# SUMO_AUTO.net
KiCad netlist of a schematic drawn in EAGLE
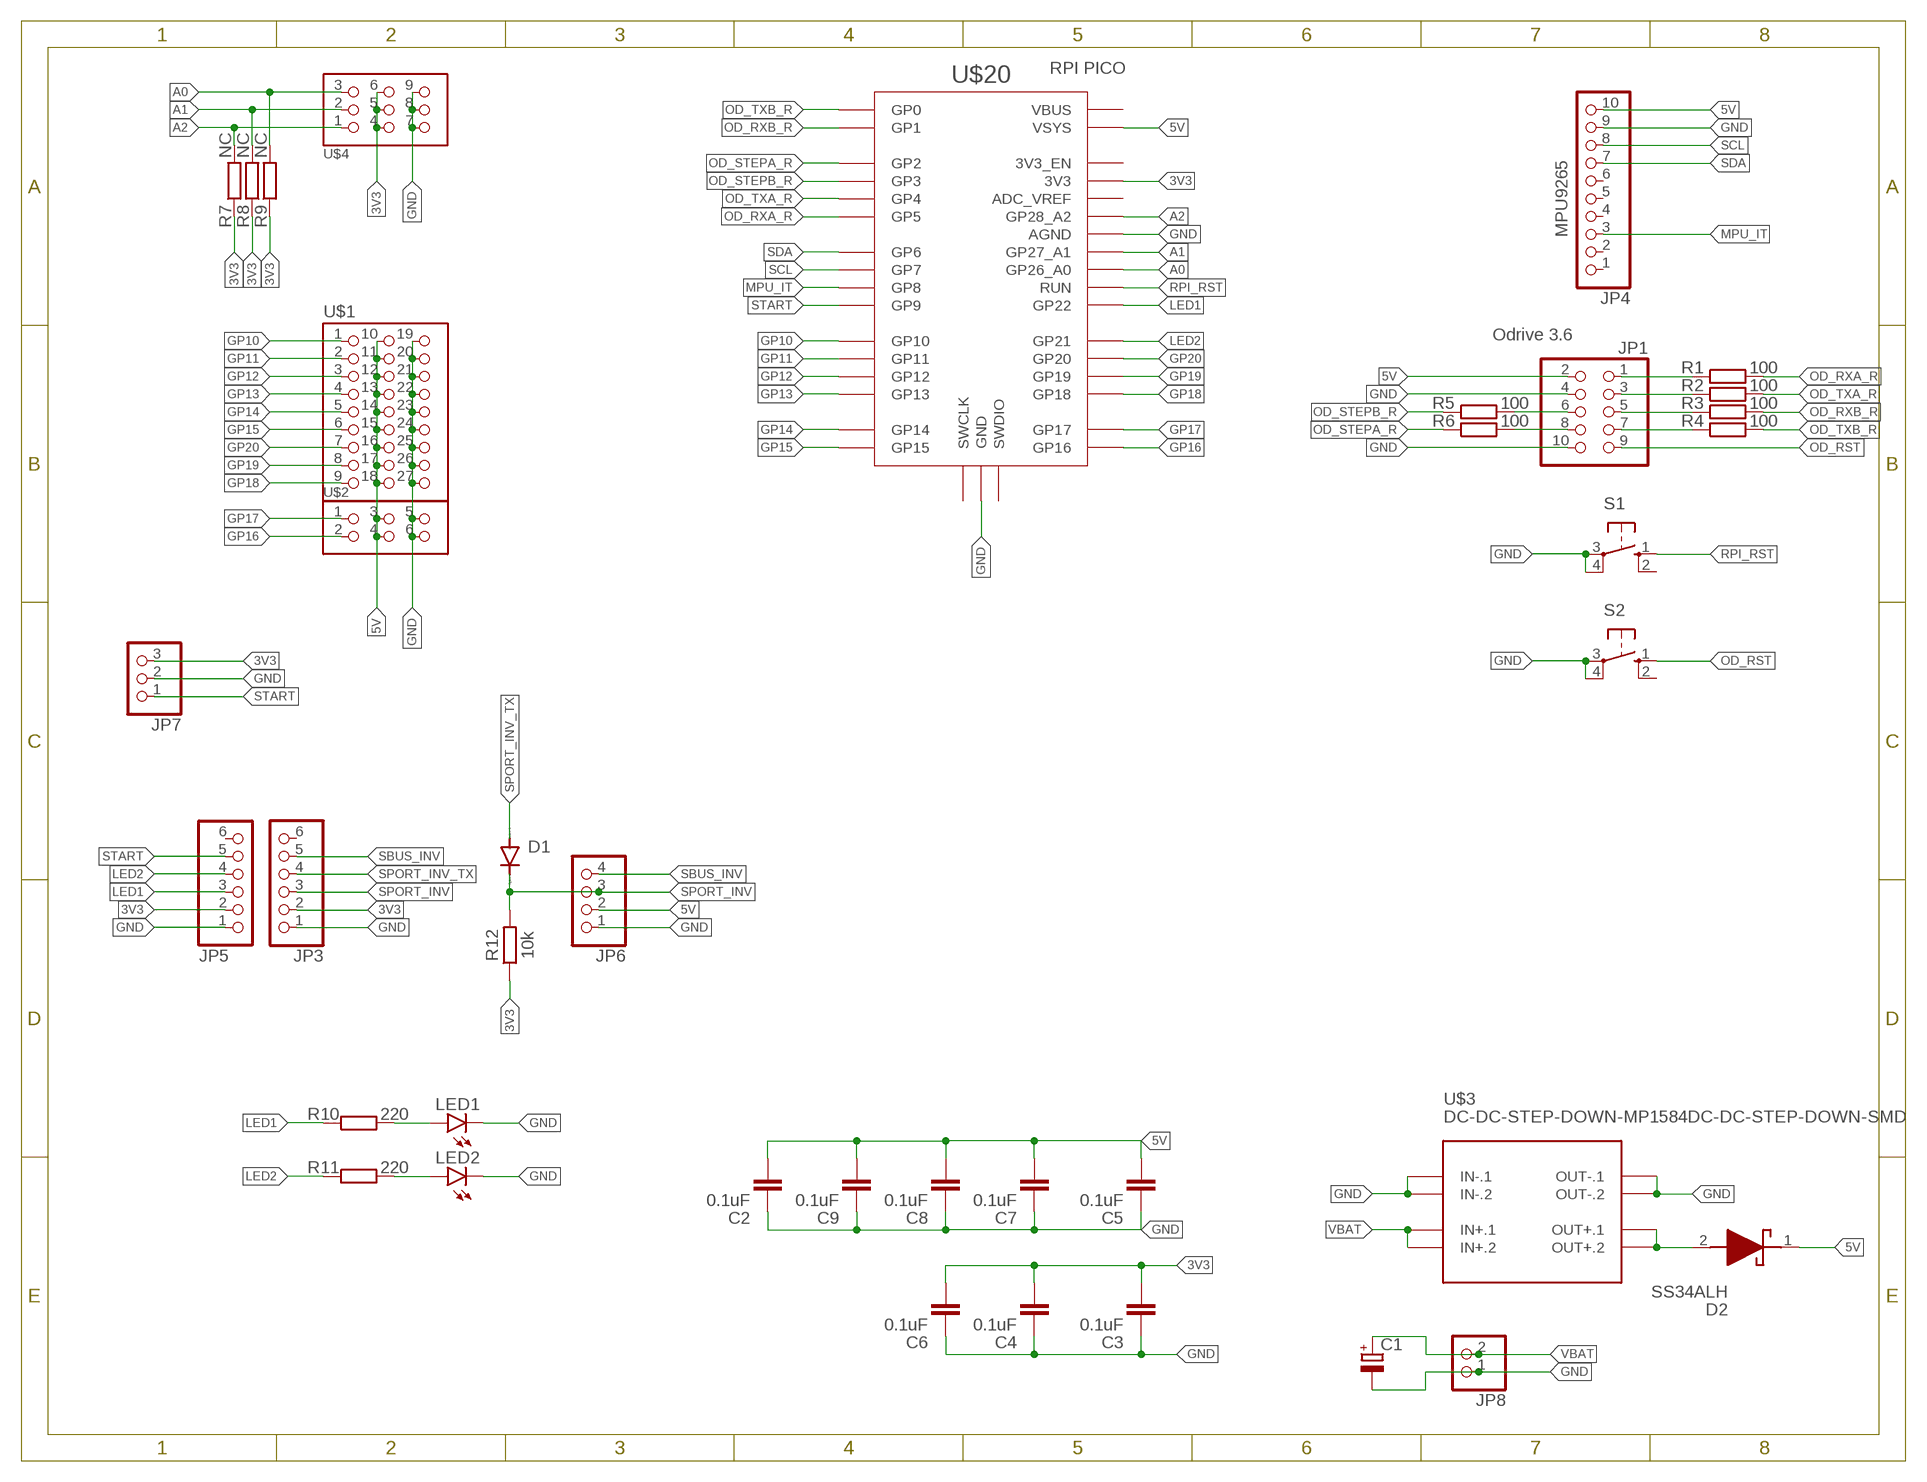
[diagram p0: schematic, sheet 1]

(export (version "E")
  (design (tool "Eeschema 10.0.6"))
  (components
    (comp (ref "C1")
      (value "C-POL_TANTALUM-2920(7443-METRIC)")
      (footprint "eagle-import:CAPMP7443X430N")
      (libsource (lib "eagle-import") (part "C-POLTANTALUM-2920(7443-METRIC)_"))
    )
    (comp (ref "C2")
      (value "0.1uF")
      (footprint "eagle-import:0805")
      (fields (field (name "JLCPCB-PART") "C14663"))
      (libsource (lib "eagle-import") (part "CCHIP-0805(2012-METRIC)_"))
    )
    (comp (ref "C3")
      (value "0.1uF")
      (footprint "eagle-import:0805")
      (fields (field (name "JLCPCB-PART") "C14663"))
      (libsource (lib "eagle-import") (part "CCHIP-0805(2012-METRIC)_"))
    )
    (comp (ref "C4")
      (value "0.1uF")
      (footprint "eagle-import:0805")
      (fields (field (name "JLCPCB-PART") "C14663"))
      (libsource (lib "eagle-import") (part "CCHIP-0805(2012-METRIC)_"))
    )
    (comp (ref "C5")
      (value "0.1uF")
      (footprint "eagle-import:0805")
      (fields (field (name "JLCPCB-PART") "C14663"))
      (libsource (lib "eagle-import") (part "CCHIP-0805(2012-METRIC)_"))
    )
    (comp (ref "C6")
      (value "0.1uF")
      (footprint "eagle-import:0805")
      (fields (field (name "JLCPCB-PART") "C14663"))
      (libsource (lib "eagle-import") (part "CCHIP-0805(2012-METRIC)_"))
    )
    (comp (ref "C7")
      (value "0.1uF")
      (footprint "eagle-import:0805")
      (fields (field (name "JLCPCB-PART") "C14663"))
      (libsource (lib "eagle-import") (part "CCHIP-0805(2012-METRIC)_"))
    )
    (comp (ref "C8")
      (value "0.1uF")
      (footprint "eagle-import:0805")
      (fields (field (name "JLCPCB-PART") "C14663"))
      (libsource (lib "eagle-import") (part "CCHIP-0805(2012-METRIC)_"))
    )
    (comp (ref "C9")
      (value "0.1uF")
      (footprint "eagle-import:0805")
      (fields (field (name "JLCPCB-PART") "C14663"))
      (libsource (lib "eagle-import") (part "CCHIP-0805(2012-METRIC)_"))
    )
    (comp (ref "D1")
      (value "BAT81")
      (footprint "eagle-import:DO34-7")
      (libsource (lib "eagle-import") (part "BAT81"))
    )
    (comp (ref "D2")
      (value "SS34ALH")
      (footprint "eagle-import:SODFL5226X100N")
      (fields (field (name "MOUSER_PART_NUMBER") "821-SS34ALH"))
      (libsource (lib "eagle-import") (part "SS34ALH"))
    )
    (comp (ref "JP1")
      (value "PINHD-2X5")
      (footprint "eagle-import:2X05")
      (libsource (lib "eagle-import") (part "PINHD-2X5"))
    )
    (comp (ref "JP3")
      (value "PINHD-1X6")
      (footprint "eagle-import:1X06")
      (libsource (lib "eagle-import") (part "PINHD-1X6"))
    )
    (comp (ref "JP4")
      (value "PINHD-1X10")
      (footprint "eagle-import:1X10")
      (libsource (lib "eagle-import") (part "PINHD-1X10"))
    )
    (comp (ref "JP5")
      (value "PINHD-1X6")
      (footprint "eagle-import:1X06")
      (libsource (lib "eagle-import") (part "PINHD-1X6"))
    )
    (comp (ref "JP6")
      (value "PINHD-1X4")
      (footprint "eagle-import:1X04")
      (libsource (lib "eagle-import") (part "PINHD-1X4"))
    )
    (comp (ref "JP7")
      (value "PINHD-1X3")
      (footprint "eagle-import:1X03")
      (libsource (lib "eagle-import") (part "PINHD-1X3"))
    )
    (comp (ref "JP8")
      (value "PINHD-1X2")
      (footprint "eagle-import:1X02")
      (libsource (lib "eagle-import") (part "PINHD-1X2"))
    )
    (comp (ref "LED1")
      (value "LEDCHIP-LED0805")
      (footprint "eagle-import:CHIP-LED0805")
      (libsource (lib "eagle-import") (part "LEDCHIP-LED0805"))
    )
    (comp (ref "LED2")
      (value "LEDCHIP-LED0805")
      (footprint "eagle-import:CHIP-LED0805")
      (libsource (lib "eagle-import") (part "LEDCHIP-LED0805"))
    )
    (comp (ref "R1")
      (value "100")
      (footprint "eagle-import:0805")
      (libsource (lib "eagle-import") (part "RCHIP-0805(2012-METRIC)_"))
    )
    (comp (ref "R2")
      (value "100")
      (footprint "eagle-import:0805")
      (libsource (lib "eagle-import") (part "RCHIP-0805(2012-METRIC)_"))
    )
    (comp (ref "R3")
      (value "100")
      (footprint "eagle-import:0805")
      (libsource (lib "eagle-import") (part "RCHIP-0805(2012-METRIC)_"))
    )
    (comp (ref "R4")
      (value "100")
      (footprint "eagle-import:0805")
      (libsource (lib "eagle-import") (part "RCHIP-0805(2012-METRIC)_"))
    )
    (comp (ref "R5")
      (value "100")
      (footprint "eagle-import:0805")
      (libsource (lib "eagle-import") (part "RCHIP-0805(2012-METRIC)_"))
    )
    (comp (ref "R6")
      (value "100")
      (footprint "eagle-import:0805")
      (libsource (lib "eagle-import") (part "RCHIP-0805(2012-METRIC)_"))
    )
    (comp (ref "R7")
      (value "NC")
      (footprint "eagle-import:0805")
      (libsource (lib "eagle-import") (part "RCHIP-0805(2012-METRIC)_"))
    )
    (comp (ref "R8")
      (value "NC")
      (footprint "eagle-import:0805")
      (libsource (lib "eagle-import") (part "RCHIP-0805(2012-METRIC)_"))
    )
    (comp (ref "R9")
      (value "NC")
      (footprint "eagle-import:0805")
      (libsource (lib "eagle-import") (part "RCHIP-0805(2012-METRIC)_"))
    )
    (comp (ref "R10")
      (value "220")
      (footprint "eagle-import:0805")
      (libsource (lib "eagle-import") (part "RCHIP-0805(2012-METRIC)_"))
    )
    (comp (ref "R11")
      (value "220")
      (footprint "eagle-import:0805")
      (libsource (lib "eagle-import") (part "RCHIP-0805(2012-METRIC)_"))
    )
    (comp (ref "R12")
      (value "10k")
      (footprint "eagle-import:0805")
      (libsource (lib "eagle-import") (part "RCHIP-0805(2012-METRIC)_"))
    )
    (comp (ref "S1")
      (value "10-XX")
      (footprint "eagle-import:B3F-10XX")
      (fields (field (name "MPN") "B3F-1000"))
      (libsource (lib "eagle-import") (part "10-XX"))
    )
    (comp (ref "S2")
      (value "10-XX")
      (footprint "eagle-import:B3F-10XX")
      (fields (field (name "MPN") "B3F-1000"))
      (libsource (lib "eagle-import") (part "10-XX"))
    )
    (comp (ref "U$1")
      (value "PIN_3X9")
      (footprint "eagle-import:PIN_3X9")
      (libsource (lib "eagle-import") (part "PIN_3X9"))
    )
    (comp (ref "U$2")
      (value "PIN_3X2")
      (footprint "eagle-import:PIN_3X2")
      (libsource (lib "eagle-import") (part "PIN_3X2"))
    )
    (comp (ref "U$3")
      (value "DC-DC-STEP-DOWN-MP1584DC-DC-STEP-DOWN-SMD")
      (footprint "eagle-import:DC-DC-STEP-DOWN-SMD")
      (libsource (lib "eagle-import") (part "DC-DC-STEP-DOWN-MP1584DC-DC-STEP-DOWN-SMD"))
    )
    (comp (ref "U$4")
      (value "PIN_3X3")
      (footprint "eagle-import:PIN_3X3")
      (libsource (lib "eagle-import") (part "PIN_3X3"))
    )
    (comp (ref "U$20")
      (value "RPI_PICO-SMD")
      (footprint "eagle-import:RPI_PICO")
      (libsource (lib "eagle-import") (part "RPI_PICO-SMD"))
    )
  )
  (nets
    (net (code "1") (name "3V3") (class "Default")
      (node (ref "C3") (pin "2") (pinfunction "2_2") (pintype "passive"))
      (node (ref "C4") (pin "2") (pinfunction "2_2") (pintype "passive"))
      (node (ref "C6") (pin "2") (pinfunction "2_2") (pintype "passive"))
      (node (ref "JP3") (pin "2") (pinfunction "2_2") (pintype "passive"))
      (node (ref "JP5") (pin "2") (pinfunction "2_2") (pintype "passive"))
      (node (ref "JP7") (pin "3") (pinfunction "3_3") (pintype "passive"))
      (node (ref "R12") (pin "1") (pinfunction "1_1") (pintype "passive"))
      (node (ref "R7") (pin "1") (pinfunction "1_1") (pintype "passive"))
      (node (ref "R8") (pin "1") (pinfunction "1_1") (pintype "passive"))
      (node (ref "R9") (pin "1") (pinfunction "1_1") (pintype "passive"))
      (node (ref "U$20") (pin "3V3") (pinfunction "3V3_3V3") (pintype "bidirectional"))
      (node (ref "U$4") (pin "4") (pinfunction "4_4") (pintype "bidirectional"))
      (node (ref "U$4") (pin "5") (pinfunction "5_5") (pintype "bidirectional"))
      (node (ref "U$4") (pin "6") (pinfunction "6_6") (pintype "bidirectional"))
    )
    (net (code "2") (name "5V") (class "Default")
      (node (ref "C2") (pin "2") (pinfunction "2_2") (pintype "passive"))
      (node (ref "C5") (pin "2") (pinfunction "2_2") (pintype "passive"))
      (node (ref "C7") (pin "2") (pinfunction "2_2") (pintype "passive"))
      (node (ref "C8") (pin "2") (pinfunction "2_2") (pintype "passive"))
      (node (ref "C9") (pin "2") (pinfunction "2_2") (pintype "passive"))
      (node (ref "D2") (pin "1") (pinfunction "K_1") (pintype "bidirectional"))
      (node (ref "JP1") (pin "2") (pinfunction "2_2") (pintype "passive"))
      (node (ref "JP4") (pin "10") (pinfunction "10_10") (pintype "passive"))
      (node (ref "JP6") (pin "2") (pinfunction "2_2") (pintype "passive"))
      (node (ref "U$1") (pin "10") (pinfunction "P$10_10") (pintype "bidirectional"))
      (node (ref "U$1") (pin "11") (pinfunction "P$11_11") (pintype "bidirectional"))
      (node (ref "U$1") (pin "12") (pinfunction "P$12_12") (pintype "bidirectional"))
      (node (ref "U$1") (pin "13") (pinfunction "P$13_13") (pintype "bidirectional"))
      (node (ref "U$1") (pin "14") (pinfunction "P$14_14") (pintype "bidirectional"))
      (node (ref "U$1") (pin "15") (pinfunction "P$15_15") (pintype "bidirectional"))
      (node (ref "U$1") (pin "16") (pinfunction "P$16_16") (pintype "bidirectional"))
      (node (ref "U$1") (pin "17") (pinfunction "P$17_17") (pintype "bidirectional"))
      (node (ref "U$1") (pin "18") (pinfunction "P$18_18") (pintype "bidirectional"))
      (node (ref "U$2") (pin "3") (pinfunction "3_3") (pintype "bidirectional"))
      (node (ref "U$2") (pin "4") (pinfunction "4_4") (pintype "bidirectional"))
      (node (ref "U$20") (pin "VSYS") (pinfunction "VSYS_VSYS") (pintype "bidirectional"))
    )
    (net (code "3") (name "A0") (class "Default")
      (node (ref "R9") (pin "2") (pinfunction "2_2") (pintype "passive"))
      (node (ref "U$20") (pin "GP26_A0") (pinfunction "GP26_A0_GP26_A0") (pintype "bidirectional"))
      (node (ref "U$4") (pin "3") (pinfunction "3_3") (pintype "bidirectional"))
    )
    (net (code "4") (name "A1") (class "Default")
      (node (ref "R8") (pin "2") (pinfunction "2_2") (pintype "passive"))
      (node (ref "U$20") (pin "GP27_A1") (pinfunction "GP27_A1_GP27_A1") (pintype "bidirectional"))
      (node (ref "U$4") (pin "2") (pinfunction "2_2") (pintype "bidirectional"))
    )
    (net (code "5") (name "A2") (class "Default")
      (node (ref "R7") (pin "2") (pinfunction "2_2") (pintype "passive"))
      (node (ref "U$20") (pin "GP28_A2") (pinfunction "GP28_A2_GP28_A2") (pintype "bidirectional"))
      (node (ref "U$4") (pin "1") (pinfunction "1_1") (pintype "bidirectional"))
    )
    (net (code "6") (name "GND") (class "Default")
      (node (ref "C1") (pin "2") (pinfunction "-_2") (pintype "passive"))
      (node (ref "C2") (pin "1") (pinfunction "1_1") (pintype "passive"))
      (node (ref "C3") (pin "1") (pinfunction "1_1") (pintype "passive"))
      (node (ref "C4") (pin "1") (pinfunction "1_1") (pintype "passive"))
      (node (ref "C5") (pin "1") (pinfunction "1_1") (pintype "passive"))
      (node (ref "C6") (pin "1") (pinfunction "1_1") (pintype "passive"))
      (node (ref "C7") (pin "1") (pinfunction "1_1") (pintype "passive"))
      (node (ref "C8") (pin "1") (pinfunction "1_1") (pintype "passive"))
      (node (ref "C9") (pin "1") (pinfunction "1_1") (pintype "passive"))
      (node (ref "JP1") (pin "10") (pinfunction "10_10") (pintype "passive"))
      (node (ref "JP1") (pin "4") (pinfunction "4_4") (pintype "passive"))
      (node (ref "JP3") (pin "1") (pinfunction "1_1") (pintype "passive"))
      (node (ref "JP4") (pin "9") (pinfunction "9_9") (pintype "passive"))
      (node (ref "JP5") (pin "1") (pinfunction "1_1") (pintype "passive"))
      (node (ref "JP6") (pin "1") (pinfunction "1_1") (pintype "passive"))
      (node (ref "JP7") (pin "2") (pinfunction "2_2") (pintype "passive"))
      (node (ref "JP8") (pin "1") (pinfunction "1_1") (pintype "passive"))
      (node (ref "LED1") (pin "C") (pinfunction "C_C") (pintype "passive"))
      (node (ref "LED2") (pin "C") (pinfunction "C_C") (pintype "passive"))
      (node (ref "S1") (pin "3") (pinfunction "P_3") (pintype "passive"))
      (node (ref "S1") (pin "4") (pinfunction "P1_4") (pintype "passive"))
      (node (ref "S2") (pin "3") (pinfunction "P_3") (pintype "passive"))
      (node (ref "S2") (pin "4") (pinfunction "P1_4") (pintype "passive"))
      (node (ref "U$1") (pin "19") (pinfunction "P$19_19") (pintype "bidirectional"))
      (node (ref "U$1") (pin "20") (pinfunction "P$20_20") (pintype "bidirectional"))
      (node (ref "U$1") (pin "21") (pinfunction "P$21_21") (pintype "bidirectional"))
      (node (ref "U$1") (pin "22") (pinfunction "P$22_22") (pintype "bidirectional"))
      (node (ref "U$1") (pin "23") (pinfunction "P$23_23") (pintype "bidirectional"))
      (node (ref "U$1") (pin "24") (pinfunction "P$24_24") (pintype "bidirectional"))
      (node (ref "U$1") (pin "25") (pinfunction "P$25_25") (pintype "bidirectional"))
      (node (ref "U$1") (pin "26") (pinfunction "P$26_26") (pintype "bidirectional"))
      (node (ref "U$1") (pin "27") (pinfunction "P$27_27") (pintype "bidirectional"))
      (node (ref "U$2") (pin "5") (pinfunction "5_5") (pintype "bidirectional"))
      (node (ref "U$2") (pin "6") (pinfunction "6_6") (pintype "bidirectional"))
      (node (ref "U$20") (pin "AGND") (pinfunction "AGND_AGND") (pintype "bidirectional"))
      (node (ref "U$20") (pin "GND@1") (pinfunction "GND_GND@1") (pintype "bidirectional"))
      (node (ref "U$20") (pin "GND@2") (pinfunction "GND_GND@2") (pintype "bidirectional"))
      (node (ref "U$20") (pin "GND@3") (pinfunction "GND_GND@3") (pintype "bidirectional"))
      (node (ref "U$20") (pin "GND@4") (pinfunction "GND_GND@4") (pintype "bidirectional"))
      (node (ref "U$20") (pin "GND@5") (pinfunction "GND_GND@5") (pintype "bidirectional"))
      (node (ref "U$20") (pin "GND@6") (pinfunction "GND_GND@6") (pintype "bidirectional"))
      (node (ref "U$20") (pin "GND@7") (pinfunction "GND_GND@7") (pintype "bidirectional"))
      (node (ref "U$20") (pin "GND@8") (pinfunction "GND_GND@8") (pintype "bidirectional"))
      (node (ref "U$3") (pin "IN-.1") (pinfunction "IN-.1_IN-.1") (pintype "bidirectional"))
      (node (ref "U$3") (pin "IN-.2") (pinfunction "IN-.2_IN-.2") (pintype "bidirectional"))
      (node (ref "U$3") (pin "OUT-.1") (pinfunction "OUT-.1_OUT-.1") (pintype "bidirectional"))
      (node (ref "U$3") (pin "OUT-.2") (pinfunction "OUT-.2_OUT-.2") (pintype "bidirectional"))
      (node (ref "U$4") (pin "7") (pinfunction "7_7") (pintype "bidirectional"))
      (node (ref "U$4") (pin "8") (pinfunction "8_8") (pintype "bidirectional"))
      (node (ref "U$4") (pin "9") (pinfunction "9_9") (pintype "bidirectional"))
    )
    (net (code "7") (name "GP10") (class "Default")
      (node (ref "U$1") (pin "1") (pinfunction "P$1_1") (pintype "bidirectional"))
      (node (ref "U$20") (pin "GP10") (pinfunction "GP10_GP10") (pintype "bidirectional"))
    )
    (net (code "8") (name "GP11") (class "Default")
      (node (ref "U$1") (pin "2") (pinfunction "P$2_2") (pintype "bidirectional"))
      (node (ref "U$20") (pin "GP11") (pinfunction "GP11_GP11") (pintype "bidirectional"))
    )
    (net (code "9") (name "GP12") (class "Default")
      (node (ref "U$1") (pin "3") (pinfunction "P$3_3") (pintype "bidirectional"))
      (node (ref "U$20") (pin "GP12") (pinfunction "GP12_GP12") (pintype "bidirectional"))
    )
    (net (code "10") (name "GP13") (class "Default")
      (node (ref "U$1") (pin "4") (pinfunction "P$4_4") (pintype "bidirectional"))
      (node (ref "U$20") (pin "GP13") (pinfunction "GP13_GP13") (pintype "bidirectional"))
    )
    (net (code "11") (name "GP14") (class "Default")
      (node (ref "U$1") (pin "5") (pinfunction "P$5_5") (pintype "bidirectional"))
      (node (ref "U$20") (pin "GP14") (pinfunction "GP14_GP14") (pintype "bidirectional"))
    )
    (net (code "12") (name "GP15") (class "Default")
      (node (ref "U$1") (pin "6") (pinfunction "P$6_6") (pintype "bidirectional"))
      (node (ref "U$20") (pin "GP15") (pinfunction "GP15_GP15") (pintype "bidirectional"))
    )
    (net (code "13") (name "GP16") (class "Default")
      (node (ref "U$2") (pin "2") (pinfunction "2_2") (pintype "bidirectional"))
      (node (ref "U$20") (pin "GP16") (pinfunction "GP16_GP16") (pintype "bidirectional"))
    )
    (net (code "14") (name "GP17") (class "Default")
      (node (ref "U$2") (pin "1") (pinfunction "1_1") (pintype "bidirectional"))
      (node (ref "U$20") (pin "GP17") (pinfunction "GP17_GP17") (pintype "bidirectional"))
    )
    (net (code "15") (name "GP18") (class "Default")
      (node (ref "U$1") (pin "9") (pinfunction "P$9_9") (pintype "bidirectional"))
      (node (ref "U$20") (pin "GP18") (pinfunction "GP18_GP18") (pintype "bidirectional"))
    )
    (net (code "16") (name "GP19") (class "Default")
      (node (ref "U$1") (pin "8") (pinfunction "P$8_8") (pintype "bidirectional"))
      (node (ref "U$20") (pin "GP19") (pinfunction "GP19_GP19") (pintype "bidirectional"))
    )
    (net (code "17") (name "GP20") (class "Default")
      (node (ref "U$1") (pin "7") (pinfunction "P$7_7") (pintype "bidirectional"))
      (node (ref "U$20") (pin "GP20") (pinfunction "GP20_GP20") (pintype "bidirectional"))
    )
    (net (code "18") (name "LED1") (class "Default")
      (node (ref "JP5") (pin "3") (pinfunction "3_3") (pintype "passive"))
      (node (ref "R10") (pin "1") (pinfunction "1_1") (pintype "passive"))
      (node (ref "U$20") (pin "GP22") (pinfunction "GP22_GP22") (pintype "bidirectional"))
    )
    (net (code "19") (name "LED2") (class "Default")
      (node (ref "JP5") (pin "4") (pinfunction "4_4") (pintype "passive"))
      (node (ref "R11") (pin "1") (pinfunction "1_1") (pintype "passive"))
      (node (ref "U$20") (pin "GP21") (pinfunction "GP21_GP21") (pintype "bidirectional"))
    )
    (net (code "20") (name "MPU_IT") (class "Default")
      (node (ref "JP4") (pin "3") (pinfunction "3_3") (pintype "passive"))
      (node (ref "U$20") (pin "GP8") (pinfunction "GP8_GP8") (pintype "bidirectional"))
    )
    (net (code "21") (name "Net-(D2-A)") (class "Default")
      (node (ref "D2") (pin "2") (pinfunction "A_2") (pintype "bidirectional"))
      (node (ref "U$3") (pin "OUT+.1") (pinfunction "OUT+.1_OUT+.1") (pintype "bidirectional"))
      (node (ref "U$3") (pin "OUT+.2") (pinfunction "OUT+.2_OUT+.2") (pintype "bidirectional"))
    )
    (net (code "22") (name "Net-(JP1-Pad1)") (class "Default")
      (node (ref "JP1") (pin "1") (pinfunction "1_1") (pintype "passive"))
      (node (ref "R1") (pin "1") (pinfunction "1_1") (pintype "passive"))
    )
    (net (code "23") (name "Net-(JP1-Pad3)") (class "Default")
      (node (ref "JP1") (pin "3") (pinfunction "3_3") (pintype "passive"))
      (node (ref "R2") (pin "1") (pinfunction "1_1") (pintype "passive"))
    )
    (net (code "24") (name "Net-(JP1-Pad5)") (class "Default")
      (node (ref "JP1") (pin "5") (pinfunction "5_5") (pintype "passive"))
      (node (ref "R3") (pin "1") (pinfunction "1_1") (pintype "passive"))
    )
    (net (code "25") (name "Net-(JP1-Pad6)") (class "Default")
      (node (ref "JP1") (pin "6") (pinfunction "6_6") (pintype "passive"))
      (node (ref "R5") (pin "2") (pinfunction "2_2") (pintype "passive"))
    )
    (net (code "26") (name "Net-(JP1-Pad7)") (class "Default")
      (node (ref "JP1") (pin "7") (pinfunction "7_7") (pintype "passive"))
      (node (ref "R4") (pin "1") (pinfunction "1_1") (pintype "passive"))
    )
    (net (code "27") (name "Net-(JP1-Pad8)") (class "Default")
      (node (ref "JP1") (pin "8") (pinfunction "8_8") (pintype "passive"))
      (node (ref "R6") (pin "2") (pinfunction "2_2") (pintype "passive"))
    )
    (net (code "28") (name "Net-(LED1-PadA)") (class "Default")
      (node (ref "LED1") (pin "A") (pinfunction "A_A") (pintype "passive"))
      (node (ref "R10") (pin "2") (pinfunction "2_2") (pintype "passive"))
    )
    (net (code "29") (name "Net-(LED2-PadA)") (class "Default")
      (node (ref "LED2") (pin "A") (pinfunction "A_A") (pintype "passive"))
      (node (ref "R11") (pin "2") (pinfunction "2_2") (pintype "passive"))
    )
    (net (code "30") (name "OD_RST") (class "Default")
      (node (ref "JP1") (pin "9") (pinfunction "9_9") (pintype "passive"))
      (node (ref "S2") (pin "1") (pinfunction "S_1") (pintype "passive"))
    )
    (net (code "31") (name "OD_RXA_R") (class "Default")
      (node (ref "R1") (pin "2") (pinfunction "2_2") (pintype "passive"))
      (node (ref "U$20") (pin "GP5") (pinfunction "GP5_GP5") (pintype "bidirectional"))
    )
    (net (code "32") (name "OD_RXB_R") (class "Default")
      (node (ref "R3") (pin "2") (pinfunction "2_2") (pintype "passive"))
      (node (ref "U$20") (pin "GP1") (pinfunction "GP1_GP1") (pintype "bidirectional"))
    )
    (net (code "33") (name "OD_STEPA_R") (class "Default")
      (node (ref "R6") (pin "1") (pinfunction "1_1") (pintype "passive"))
      (node (ref "U$20") (pin "GP2") (pinfunction "GP2_GP2") (pintype "bidirectional"))
    )
    (net (code "34") (name "OD_STEPB_R") (class "Default")
      (node (ref "R5") (pin "1") (pinfunction "1_1") (pintype "passive"))
      (node (ref "U$20") (pin "GP3") (pinfunction "GP3_GP3") (pintype "bidirectional"))
    )
    (net (code "35") (name "OD_TXA_R") (class "Default")
      (node (ref "R2") (pin "2") (pinfunction "2_2") (pintype "passive"))
      (node (ref "U$20") (pin "GP4") (pinfunction "GP4_GP4") (pintype "bidirectional"))
    )
    (net (code "36") (name "OD_TXB_R") (class "Default")
      (node (ref "R4") (pin "2") (pinfunction "2_2") (pintype "passive"))
      (node (ref "U$20") (pin "GP0") (pinfunction "GP0_GP0") (pintype "bidirectional"))
    )
    (net (code "37") (name "RPI_RST") (class "Default")
      (node (ref "S1") (pin "1") (pinfunction "S_1") (pintype "passive"))
      (node (ref "U$20") (pin "RUN") (pinfunction "RUN_RUN") (pintype "bidirectional"))
    )
    (net (code "38") (name "SBUS_INV") (class "Default")
      (node (ref "JP3") (pin "5") (pinfunction "5_5") (pintype "passive"))
      (node (ref "JP6") (pin "4") (pinfunction "4_4") (pintype "passive"))
    )
    (net (code "39") (name "SCL") (class "Default")
      (node (ref "JP4") (pin "8") (pinfunction "8_8") (pintype "passive"))
      (node (ref "U$20") (pin "GP7") (pinfunction "GP7_GP7") (pintype "bidirectional"))
    )
    (net (code "40") (name "SDA") (class "Default")
      (node (ref "JP4") (pin "7") (pinfunction "7_7") (pintype "passive"))
      (node (ref "U$20") (pin "GP6") (pinfunction "GP6_GP6") (pintype "bidirectional"))
    )
    (net (code "41") (name "SPORT_INV") (class "Default")
      (node (ref "D1") (pin "C") (pinfunction "C_C") (pintype "passive"))
      (node (ref "JP3") (pin "3") (pinfunction "3_3") (pintype "passive"))
      (node (ref "JP6") (pin "3") (pinfunction "3_3") (pintype "passive"))
      (node (ref "R12") (pin "2") (pinfunction "2_2") (pintype "passive"))
    )
    (net (code "42") (name "SPORT_INV_TX") (class "Default")
      (node (ref "D1") (pin "A") (pinfunction "A_A") (pintype "passive"))
      (node (ref "JP3") (pin "4") (pinfunction "4_4") (pintype "passive"))
    )
    (net (code "43") (name "START") (class "Default")
      (node (ref "JP5") (pin "5") (pinfunction "5_5") (pintype "passive"))
      (node (ref "JP7") (pin "1") (pinfunction "1_1") (pintype "passive"))
      (node (ref "U$20") (pin "GP9") (pinfunction "GP9_GP9") (pintype "bidirectional"))
    )
    (net (code "44") (name "VBAT") (class "Default")
      (node (ref "C1") (pin "1") (pinfunction "+_1") (pintype "passive"))
      (node (ref "JP8") (pin "2") (pinfunction "2_2") (pintype "passive"))
      (node (ref "U$3") (pin "IN+.1") (pinfunction "IN+.1_IN+.1") (pintype "bidirectional"))
      (node (ref "U$3") (pin "IN+.2") (pinfunction "IN+.2_IN+.2") (pintype "bidirectional"))
    )
    (net (code "45") (name "unconnected-(JP3-Pad6)") (class "Default")
      (node (ref "JP3") (pin "6") (pinfunction "6_6") (pintype "passive"))
    )
    (net (code "46") (name "unconnected-(JP4-Pad1)") (class "Default")
      (node (ref "JP4") (pin "1") (pinfunction "1_1") (pintype "passive"))
    )
    (net (code "47") (name "unconnected-(JP4-Pad2)") (class "Default")
      (node (ref "JP4") (pin "2") (pinfunction "2_2") (pintype "passive"))
    )
    (net (code "48") (name "unconnected-(JP4-Pad4)") (class "Default")
      (node (ref "JP4") (pin "4") (pinfunction "4_4") (pintype "passive"))
    )
    (net (code "49") (name "unconnected-(JP4-Pad5)") (class "Default")
      (node (ref "JP4") (pin "5") (pinfunction "5_5") (pintype "passive"))
    )
    (net (code "50") (name "unconnected-(JP4-Pad6)") (class "Default")
      (node (ref "JP4") (pin "6") (pinfunction "6_6") (pintype "passive"))
    )
    (net (code "51") (name "unconnected-(JP5-Pad6)") (class "Default")
      (node (ref "JP5") (pin "6") (pinfunction "6_6") (pintype "passive"))
    )
    (net (code "52") (name "unconnected-(S1-S1-Pad2)") (class "Default")
      (node (ref "S1") (pin "2") (pinfunction "S1_2") (pintype "passive"))
    )
    (net (code "53") (name "unconnected-(S2-S1-Pad2)") (class "Default")
      (node (ref "S2") (pin "2") (pinfunction "S1_2") (pintype "passive"))
    )
    (net (code "54") (name "unconnected-(U$20-Pad3V3_EN)") (class "Default")
      (node (ref "U$20") (pin "3V3_EN") (pinfunction "3V3_EN_3V3_EN") (pintype "bidirectional"))
    )
    (net (code "55") (name "unconnected-(U$20-PadADC_VREF)") (class "Default")
      (node (ref "U$20") (pin "ADC_VREF") (pinfunction "ADC_VREF_ADC_VREF") (pintype "bidirectional"))
    )
    (net (code "56") (name "unconnected-(U$20-PadSWCLK)") (class "Default")
      (node (ref "U$20") (pin "SWCLK") (pinfunction "SWCLK_SWCLK") (pintype "bidirectional"))
    )
    (net (code "57") (name "unconnected-(U$20-PadSWDIO)") (class "Default")
      (node (ref "U$20") (pin "SWDIO") (pinfunction "SWDIO_SWDIO") (pintype "bidirectional"))
    )
    (net (code "58") (name "unconnected-(U$20-PadVBUS)") (class "Default")
      (node (ref "U$20") (pin "VBUS") (pinfunction "VBUS_VBUS") (pintype "bidirectional"))
    )
  )
)
